# AD4111_1.net
KiCad netlist of a schematic drawn in Altium Designer
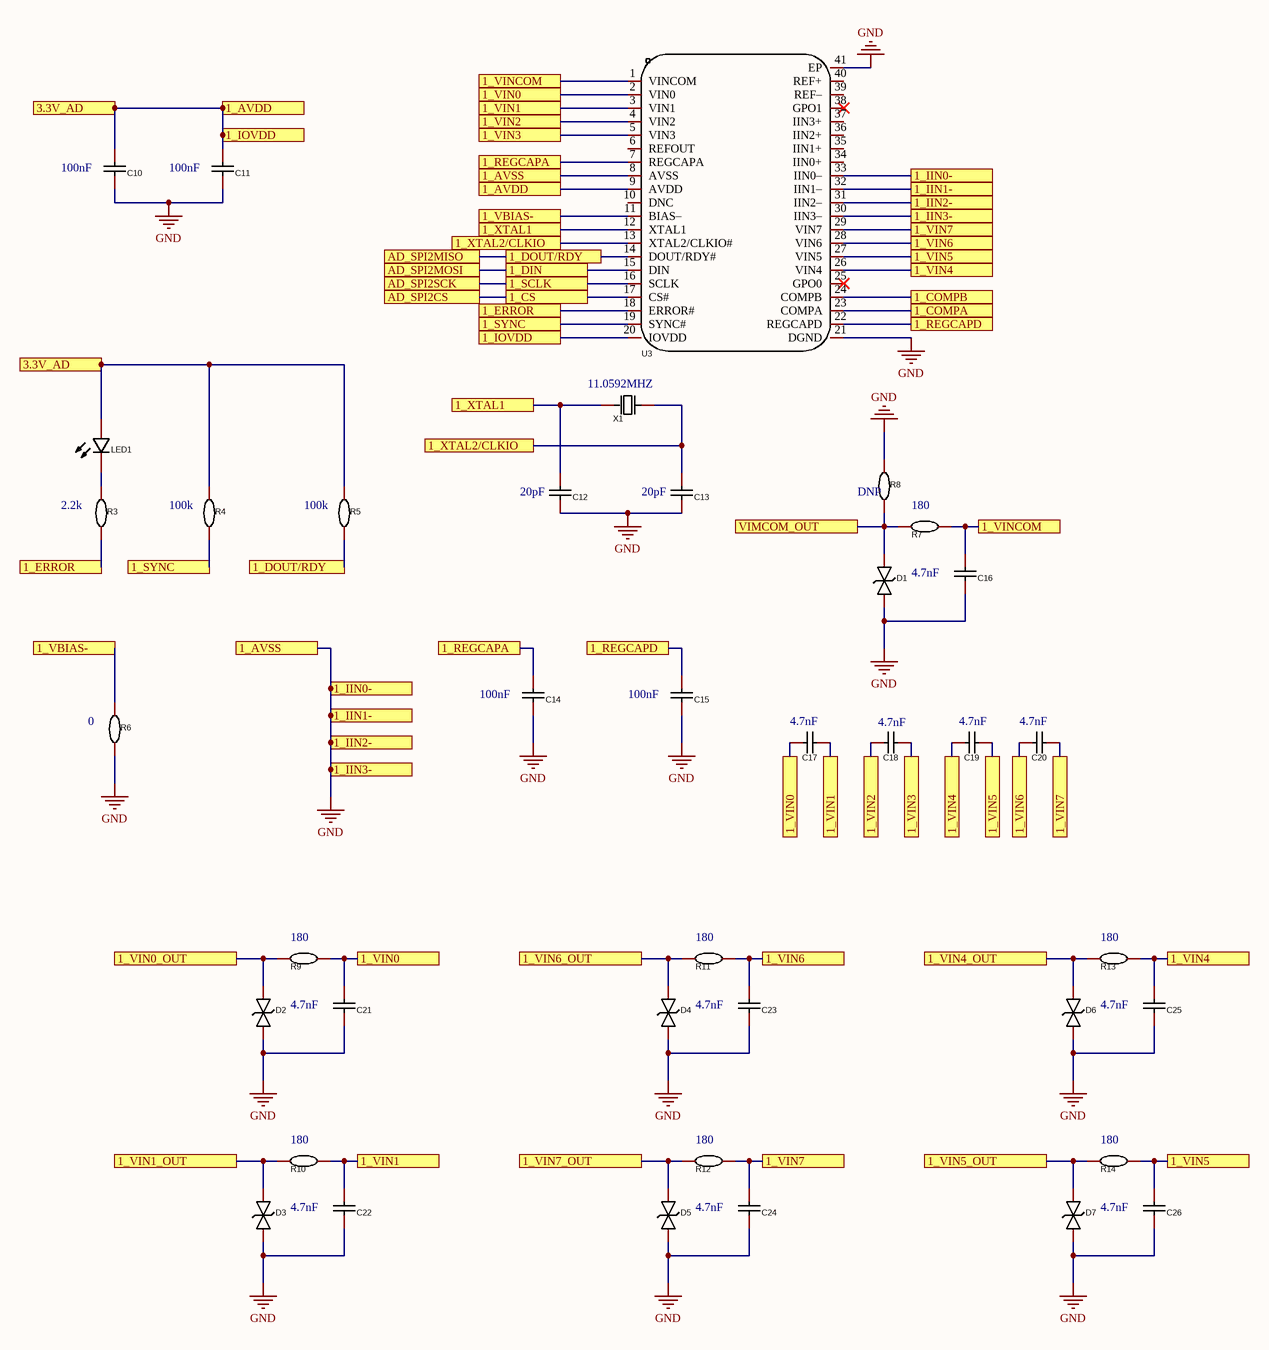
[diagram p0: AD4111_1.SchDoc]

(export (version "E")
  (design (tool "Eeschema 10.0.6"))
  (components
    (comp (ref "C10")
      (value "100nF")
      (footprint "C0603")
      (description "0603电容")
      (fields (field (name "MANUFACTURER") "FH(风华)") (field (name "MANUFACTURER PART") "0603B104K500NT"))
      (libsource (lib "LC_Components") (part "0603B104K500NT"))
    )
    (comp (ref "C11")
      (value "100nF")
      (footprint "C0603")
      (description "0603电容")
      (fields (field (name "MANUFACTURER") "FH(风华)") (field (name "MANUFACTURER PART") "0603B104K500NT"))
      (libsource (lib "LC_Components") (part "0603B104K500NT"))
    )
    (comp (ref "C12")
      (value "20pF")
      (footprint "C0603")
      (description "0603电容")
      (fields (field (name "MANUFACTURER") "FH(风华)") (field (name "MANUFACTURER PART") "0603B104K500NT"))
      (libsource (lib "LC_Components") (part "0603B104K500NT"))
    )
    (comp (ref "C13")
      (value "20pF")
      (footprint "C0603")
      (description "0603电容")
      (fields (field (name "MANUFACTURER") "FH(风华)") (field (name "MANUFACTURER PART") "0603B104K500NT"))
      (libsource (lib "LC_Components") (part "0603B104K500NT"))
    )
    (comp (ref "C14")
      (value "100nF")
      (footprint "C0603")
      (description "0603电容")
      (fields (field (name "MANUFACTURER") "FH(风华)") (field (name "MANUFACTURER PART") "0603B104K500NT"))
      (libsource (lib "LC_Components") (part "0603B104K500NT"))
    )
    (comp (ref "C15")
      (value "100nF")
      (footprint "C0603")
      (description "0603电容")
      (fields (field (name "MANUFACTURER") "FH(风华)") (field (name "MANUFACTURER PART") "0603B104K500NT"))
      (libsource (lib "LC_Components") (part "0603B104K500NT"))
    )
    (comp (ref "C16")
      (value "4.7nF")
      (footprint "C0603")
      (description "0603电容")
      (fields (field (name "MANUFACTURER") "FH(风华)") (field (name "MANUFACTURER PART") "0603B104K500NT"))
      (libsource (lib "LC_Components") (part "0603B104K500NT"))
    )
    (comp (ref "C17")
      (value "4.7nF")
      (footprint "C0603")
      (description "0603电容")
      (fields (field (name "MANUFACTURER") "FH(风华)") (field (name "MANUFACTURER PART") "0603B104K500NT"))
      (libsource (lib "LC_Components") (part "0603B104K500NT"))
    )
    (comp (ref "C18")
      (value "4.7nF")
      (footprint "C0603")
      (description "0603电容")
      (fields (field (name "MANUFACTURER") "FH(风华)") (field (name "MANUFACTURER PART") "0603B104K500NT"))
      (libsource (lib "LC_Components") (part "0603B104K500NT"))
    )
    (comp (ref "C19")
      (value "4.7nF")
      (footprint "C0603")
      (description "0603电容")
      (fields (field (name "MANUFACTURER") "FH(风华)") (field (name "MANUFACTURER PART") "0603B104K500NT"))
      (libsource (lib "LC_Components") (part "0603B104K500NT"))
    )
    (comp (ref "C20")
      (value "4.7nF")
      (footprint "C0603")
      (description "0603电容")
      (fields (field (name "MANUFACTURER") "FH(风华)") (field (name "MANUFACTURER PART") "0603B104K500NT"))
      (libsource (lib "LC_Components") (part "0603B104K500NT"))
    )
    (comp (ref "C21")
      (value "4.7nF")
      (footprint "C0603")
      (description "0603电容")
      (fields (field (name "MANUFACTURER") "FH(风华)") (field (name "MANUFACTURER PART") "0603B104K500NT"))
      (libsource (lib "LC_Components") (part "0603B104K500NT"))
    )
    (comp (ref "C22")
      (value "4.7nF")
      (footprint "C0603")
      (description "0603电容")
      (fields (field (name "MANUFACTURER") "FH(风华)") (field (name "MANUFACTURER PART") "0603B104K500NT"))
      (libsource (lib "LC_Components") (part "0603B104K500NT"))
    )
    (comp (ref "C23")
      (value "4.7nF")
      (footprint "C0603")
      (description "0603电容")
      (fields (field (name "MANUFACTURER") "FH(风华)") (field (name "MANUFACTURER PART") "0603B104K500NT"))
      (libsource (lib "LC_Components") (part "0603B104K500NT"))
    )
    (comp (ref "C24")
      (value "4.7nF")
      (footprint "C0603")
      (description "0603电容")
      (fields (field (name "MANUFACTURER") "FH(风华)") (field (name "MANUFACTURER PART") "0603B104K500NT"))
      (libsource (lib "LC_Components") (part "0603B104K500NT"))
    )
    (comp (ref "C25")
      (value "4.7nF")
      (footprint "C0603")
      (description "0603电容")
      (fields (field (name "MANUFACTURER") "FH(风华)") (field (name "MANUFACTURER PART") "0603B104K500NT"))
      (libsource (lib "LC_Components") (part "0603B104K500NT"))
    )
    (comp (ref "C26")
      (value "4.7nF")
      (footprint "C0603")
      (description "0603电容")
      (fields (field (name "MANUFACTURER") "FH(风华)") (field (name "MANUFACTURER PART") "0603B104K500NT"))
      (libsource (lib "LC_Components") (part "0603B104K500NT"))
    )
    (comp (ref "D1")
      (value "SMAJ33CA_C908829")
      (footprint "SMA_L4.4-W2.8-LS5.1-BI")
      (description "SMAJ33CA")
      (fields (field (name "MANUFACTURER") "GOODWORK(固得沃克)"))
      (libsource (lib "LC_Components") (part "SMAJ33CA_C908829"))
    )
    (comp (ref "D2")
      (value "SMAJ33CA_C908829")
      (footprint "SMA_L4.4-W2.8-LS5.1-BI")
      (description "SMAJ33CA")
      (fields (field (name "MANUFACTURER") "GOODWORK(固得沃克)"))
      (libsource (lib "LC_Components") (part "SMAJ33CA_C908829"))
    )
    (comp (ref "D3")
      (value "SMAJ33CA_C908829")
      (footprint "SMA_L4.4-W2.8-LS5.1-BI")
      (description "SMAJ33CA")
      (fields (field (name "MANUFACTURER") "GOODWORK(固得沃克)"))
      (libsource (lib "LC_Components") (part "SMAJ33CA_C908829"))
    )
    (comp (ref "D4")
      (value "SMAJ33CA_C908829")
      (footprint "SMA_L4.4-W2.8-LS5.1-BI")
      (description "SMAJ33CA")
      (fields (field (name "MANUFACTURER") "GOODWORK(固得沃克)"))
      (libsource (lib "LC_Components") (part "SMAJ33CA_C908829"))
    )
    (comp (ref "D5")
      (value "SMAJ33CA_C908829")
      (footprint "SMA_L4.4-W2.8-LS5.1-BI")
      (description "SMAJ33CA")
      (fields (field (name "MANUFACTURER") "GOODWORK(固得沃克)"))
      (libsource (lib "LC_Components") (part "SMAJ33CA_C908829"))
    )
    (comp (ref "D6")
      (value "SMAJ33CA_C908829")
      (footprint "SMA_L4.4-W2.8-LS5.1-BI")
      (description "SMAJ33CA")
      (fields (field (name "MANUFACTURER") "GOODWORK(固得沃克)"))
      (libsource (lib "LC_Components") (part "SMAJ33CA_C908829"))
    )
    (comp (ref "D7")
      (value "SMAJ33CA_C908829")
      (footprint "SMA_L4.4-W2.8-LS5.1-BI")
      (description "SMAJ33CA")
      (fields (field (name "MANUFACTURER") "GOODWORK(固得沃克)"))
      (libsource (lib "LC_Components") (part "SMAJ33CA_C908829"))
    )
    (comp (ref "LED1")
      (value "NCD0603R1_C84263")
      (footprint "LED0603-RD_RED")
      (description "LED")
      (fields (field (name "MANUFACTURER") "国星光电") (field (name "MANUFACTURER PART") "NCD0603R1"))
      (libsource (lib "LC_Components") (part "NCD0603R1_C84263"))
    )
    (comp (ref "R3")
      (value "2.2k")
      (footprint "R0603")
      (description "0603电阻")
      (fields
        (field (name "MANUFACTURER") "UNI-ROYAL(厚声)")
        (field (name "MANUFACTURER PART") "0603WAF1002T5E")
      )
      (libsource (lib "LC_Components") (part "0603WAF1002T5E"))
    )
    (comp (ref "R4")
      (value "100k")
      (footprint "R0603")
      (description "0603电阻")
      (fields
        (field (name "MANUFACTURER") "UNI-ROYAL(厚声)")
        (field (name "MANUFACTURER PART") "0603WAF1002T5E")
      )
      (libsource (lib "LC_Components") (part "0603WAF1002T5E"))
    )
    (comp (ref "R5")
      (value "100k")
      (footprint "R0603")
      (description "0603电阻")
      (fields
        (field (name "MANUFACTURER") "UNI-ROYAL(厚声)")
        (field (name "MANUFACTURER PART") "0603WAF1002T5E")
      )
      (libsource (lib "LC_Components") (part "0603WAF1002T5E"))
    )
    (comp (ref "R6")
      (value "0")
      (footprint "R0603")
      (description "0603电阻")
      (fields
        (field (name "MANUFACTURER") "UNI-ROYAL(厚声)")
        (field (name "MANUFACTURER PART") "0603WAF1002T5E")
      )
      (libsource (lib "LC_Components") (part "0603WAF1002T5E"))
    )
    (comp (ref "R7")
      (value "180")
      (footprint "R0603")
      (description "0603电阻")
      (fields
        (field (name "MANUFACTURER") "UNI-ROYAL(厚声)")
        (field (name "MANUFACTURER PART") "0603WAF1002T5E")
      )
      (libsource (lib "LC_Components") (part "0603WAF1002T5E"))
    )
    (comp (ref "R8")
      (value "DNP")
      (footprint "R0603")
      (description "0603电阻")
      (fields
        (field (name "MANUFACTURER") "UNI-ROYAL(厚声)")
        (field (name "MANUFACTURER PART") "0603WAF1002T5E")
      )
      (libsource (lib "LC_Components") (part "0603WAF1002T5E"))
    )
    (comp (ref "R9")
      (value "180")
      (footprint "R0603")
      (description "0603电阻")
      (fields
        (field (name "MANUFACTURER") "UNI-ROYAL(厚声)")
        (field (name "MANUFACTURER PART") "0603WAF1002T5E")
      )
      (libsource (lib "LC_Components") (part "0603WAF1002T5E"))
    )
    (comp (ref "R10")
      (value "180")
      (footprint "R0603")
      (description "0603电阻")
      (fields
        (field (name "MANUFACTURER") "UNI-ROYAL(厚声)")
        (field (name "MANUFACTURER PART") "0603WAF1002T5E")
      )
      (libsource (lib "LC_Components") (part "0603WAF1002T5E"))
    )
    (comp (ref "R11")
      (value "180")
      (footprint "R0603")
      (description "0603电阻")
      (fields
        (field (name "MANUFACTURER") "UNI-ROYAL(厚声)")
        (field (name "MANUFACTURER PART") "0603WAF1002T5E")
      )
      (libsource (lib "LC_Components") (part "0603WAF1002T5E"))
    )
    (comp (ref "R12")
      (value "180")
      (footprint "R0603")
      (description "0603电阻")
      (fields
        (field (name "MANUFACTURER") "UNI-ROYAL(厚声)")
        (field (name "MANUFACTURER PART") "0603WAF1002T5E")
      )
      (libsource (lib "LC_Components") (part "0603WAF1002T5E"))
    )
    (comp (ref "R13")
      (value "180")
      (footprint "R0603")
      (description "0603电阻")
      (fields
        (field (name "MANUFACTURER") "UNI-ROYAL(厚声)")
        (field (name "MANUFACTURER PART") "0603WAF1002T5E")
      )
      (libsource (lib "LC_Components") (part "0603WAF1002T5E"))
    )
    (comp (ref "R14")
      (value "180")
      (footprint "R0603")
      (description "0603电阻")
      (fields
        (field (name "MANUFACTURER") "UNI-ROYAL(厚声)")
        (field (name "MANUFACTURER PART") "0603WAF1002T5E")
      )
      (libsource (lib "LC_Components") (part "0603WAF1002T5E"))
    )
    (comp (ref "U3")
      (value "AD4111BCPZ")
      (footprint "LFCSP-40_L6.0-W6.0-P0.50-TL-EP4.6")
      (fields (field (name "MANUFACTURER") "ADI(亚德诺)"))
      (libsource (lib "LC_Components") (part "AD4111BCPZ"))
    )
    (comp (ref "X1")
      (value "11.0592MHZ")
      (footprint "OSC-SMD_L5.0-W3.2")
      (description "11.0592MHZ晶振")
      (fields
        (field (name "MANUFACTURER") "YXC(扬兴晶振)")
        (field (name "MANUFACTURER PART") "X5032110592MSB2GI")
      )
      (libsource (lib "LC_Components") (part "X5032110592MSB2GI"))
    )
  )
  (nets
    (net (code "1") (name "/1_AVDD") (class "Default")
      (node (ref "C10") (pin "2") (pinfunction "2_2") (pintype "passive"))
      (node (ref "C11") (pin "2") (pinfunction "2_2") (pintype "passive"))
      (node (ref "LED1") (pin "2") (pinfunction "A_2") (pintype "passive"))
      (node (ref "R4") (pin "2") (pinfunction "2_2") (pintype "passive"))
      (node (ref "R5") (pin "2") (pinfunction "2_2") (pintype "passive"))
      (node (ref "U3") (pin "20") (pinfunction "IOVDD_20") (pintype "passive"))
      (node (ref "U3") (pin "9") (pinfunction "AVDD_9") (pintype "passive"))
    )
    (net (code "2") (name "/1_COMPA") (class "Default")
      (node (ref "U3") (pin "23") (pinfunction "COMPA_23") (pintype "passive"))
    )
    (net (code "3") (name "/1_COMPB") (class "Default")
      (node (ref "U3") (pin "24") (pinfunction "COMPB_24") (pintype "passive"))
    )
    (net (code "4") (name "/1_CS") (class "Default")
      (node (ref "U3") (pin "17") (pinfunction "CS#_17") (pintype "passive"))
    )
    (net (code "5") (name "/1_DIN") (class "Default")
      (node (ref "U3") (pin "15") (pinfunction "DIN_15") (pintype "passive"))
    )
    (net (code "6") (name "/1_DOUT{slash}RDY") (class "Default")
      (node (ref "R5") (pin "1") (pinfunction "1_1") (pintype "passive"))
      (node (ref "U3") (pin "14") (pinfunction "DOUT/RDY#_14") (pintype "passive"))
    )
    (net (code "7") (name "/1_ERROR") (class "Default")
      (node (ref "R3") (pin "1") (pinfunction "1_1") (pintype "passive"))
      (node (ref "U3") (pin "18") (pinfunction "ERROR#_18") (pintype "passive"))
    )
    (net (code "8") (name "/1_REGCAPA") (class "Default")
      (node (ref "C14") (pin "2") (pinfunction "2_2") (pintype "passive"))
      (node (ref "U3") (pin "7") (pinfunction "REGCAPA_7") (pintype "passive"))
    )
    (net (code "9") (name "/1_REGCAPD") (class "Default")
      (node (ref "C15") (pin "2") (pinfunction "2_2") (pintype "passive"))
      (node (ref "U3") (pin "22") (pinfunction "REGCAPD_22") (pintype "passive"))
    )
    (net (code "10") (name "/1_SCLK") (class "Default")
      (node (ref "U3") (pin "16") (pinfunction "SCLK_16") (pintype "passive"))
    )
    (net (code "11") (name "/1_SYNC") (class "Default")
      (node (ref "R4") (pin "1") (pinfunction "1_1") (pintype "passive"))
      (node (ref "U3") (pin "19") (pinfunction "SYNC#_19") (pintype "passive"))
    )
    (net (code "12") (name "/1_VBIAS-") (class "Default")
      (node (ref "R6") (pin "2") (pinfunction "2_2") (pintype "passive"))
      (node (ref "U3") (pin "11") (pinfunction "BIAS–_11") (pintype "passive"))
    )
    (net (code "13") (name "/1_VIN0") (class "Default")
      (node (ref "C17") (pin "1") (pinfunction "1_1") (pintype "passive"))
      (node (ref "C21") (pin "2") (pinfunction "2_2") (pintype "passive"))
      (node (ref "R9") (pin "2") (pinfunction "2_2") (pintype "passive"))
      (node (ref "U3") (pin "2") (pinfunction "VIN0_2") (pintype "passive"))
    )
    (net (code "14") (name "/1_VIN0_OUT") (class "Default")
      (node (ref "D2") (pin "1") (pinfunction "1_1") (pintype "passive"))
      (node (ref "R9") (pin "1") (pinfunction "1_1") (pintype "passive"))
    )
    (net (code "15") (name "/1_VIN1") (class "Default")
      (node (ref "C17") (pin "2") (pinfunction "2_2") (pintype "passive"))
      (node (ref "C22") (pin "2") (pinfunction "2_2") (pintype "passive"))
      (node (ref "R10") (pin "2") (pinfunction "2_2") (pintype "passive"))
      (node (ref "U3") (pin "3") (pinfunction "VIN1_3") (pintype "passive"))
    )
    (net (code "16") (name "/1_VIN1_OUT") (class "Default")
      (node (ref "D3") (pin "1") (pinfunction "1_1") (pintype "passive"))
      (node (ref "R10") (pin "1") (pinfunction "1_1") (pintype "passive"))
    )
    (net (code "17") (name "/1_VIN2") (class "Default")
      (node (ref "C18") (pin "1") (pinfunction "1_1") (pintype "passive"))
      (node (ref "U3") (pin "4") (pinfunction "VIN2_4") (pintype "passive"))
    )
    (net (code "18") (name "/1_VIN3") (class "Default")
      (node (ref "C18") (pin "2") (pinfunction "2_2") (pintype "passive"))
      (node (ref "U3") (pin "5") (pinfunction "VIN3_5") (pintype "passive"))
    )
    (net (code "19") (name "/1_VIN4") (class "Default")
      (node (ref "C19") (pin "1") (pinfunction "1_1") (pintype "passive"))
      (node (ref "C25") (pin "2") (pinfunction "2_2") (pintype "passive"))
      (node (ref "R13") (pin "2") (pinfunction "2_2") (pintype "passive"))
      (node (ref "U3") (pin "26") (pinfunction "VIN4_26") (pintype "passive"))
    )
    (net (code "20") (name "/1_VIN4_OUT") (class "Default")
      (node (ref "D6") (pin "1") (pinfunction "1_1") (pintype "passive"))
      (node (ref "R13") (pin "1") (pinfunction "1_1") (pintype "passive"))
    )
    (net (code "21") (name "/1_VIN5") (class "Default")
      (node (ref "C19") (pin "2") (pinfunction "2_2") (pintype "passive"))
      (node (ref "C26") (pin "2") (pinfunction "2_2") (pintype "passive"))
      (node (ref "R14") (pin "2") (pinfunction "2_2") (pintype "passive"))
      (node (ref "U3") (pin "27") (pinfunction "VIN5_27") (pintype "passive"))
    )
    (net (code "22") (name "/1_VIN5_OUT") (class "Default")
      (node (ref "D7") (pin "1") (pinfunction "1_1") (pintype "passive"))
      (node (ref "R14") (pin "1") (pinfunction "1_1") (pintype "passive"))
    )
    (net (code "23") (name "/1_VIN6") (class "Default")
      (node (ref "C20") (pin "1") (pinfunction "1_1") (pintype "passive"))
      (node (ref "C23") (pin "2") (pinfunction "2_2") (pintype "passive"))
      (node (ref "R11") (pin "2") (pinfunction "2_2") (pintype "passive"))
      (node (ref "U3") (pin "28") (pinfunction "VIN6_28") (pintype "passive"))
    )
    (net (code "24") (name "/1_VIN6_OUT") (class "Default")
      (node (ref "D4") (pin "1") (pinfunction "1_1") (pintype "passive"))
      (node (ref "R11") (pin "1") (pinfunction "1_1") (pintype "passive"))
    )
    (net (code "25") (name "/1_VIN7") (class "Default")
      (node (ref "C20") (pin "2") (pinfunction "2_2") (pintype "passive"))
      (node (ref "C24") (pin "2") (pinfunction "2_2") (pintype "passive"))
      (node (ref "R12") (pin "2") (pinfunction "2_2") (pintype "passive"))
      (node (ref "U3") (pin "29") (pinfunction "VIN7_29") (pintype "passive"))
    )
    (net (code "26") (name "/1_VIN7_OUT") (class "Default")
      (node (ref "D5") (pin "1") (pinfunction "1_1") (pintype "passive"))
      (node (ref "R12") (pin "1") (pinfunction "1_1") (pintype "passive"))
    )
    (net (code "27") (name "/1_VINCOM") (class "Default")
      (node (ref "C16") (pin "2") (pinfunction "2_2") (pintype "passive"))
      (node (ref "R7") (pin "2") (pinfunction "2_2") (pintype "passive"))
      (node (ref "U3") (pin "1") (pinfunction "VINCOM_1") (pintype "passive"))
    )
    (net (code "28") (name "/1_XTAL1") (class "Default")
      (node (ref "C12") (pin "2") (pinfunction "2_2") (pintype "passive"))
      (node (ref "U3") (pin "12") (pinfunction "XTAL1_12") (pintype "passive"))
      (node (ref "X1") (pin "1") (pinfunction "OSC1_1") (pintype "passive"))
    )
    (net (code "29") (name "/1_XTAL2{slash}CLKIO") (class "Default")
      (node (ref "C13") (pin "2") (pinfunction "2_2") (pintype "passive"))
      (node (ref "U3") (pin "13") (pinfunction "XTAL2/CLKIO#_13") (pintype "passive"))
      (node (ref "X1") (pin "2") (pinfunction "OSC2_2") (pintype "passive"))
    )
    (net (code "30") (name "/VIMCOM_OUT") (class "Default")
      (node (ref "D1") (pin "1") (pinfunction "1_1") (pintype "passive"))
      (node (ref "R7") (pin "1") (pinfunction "1_1") (pintype "passive"))
      (node (ref "R8") (pin "1") (pinfunction "1_1") (pintype "passive"))
    )
    (net (code "31") (name "GND") (class "Default")
      (node (ref "C10") (pin "1") (pinfunction "1_1") (pintype "passive"))
      (node (ref "C11") (pin "1") (pinfunction "1_1") (pintype "passive"))
      (node (ref "C12") (pin "1") (pinfunction "1_1") (pintype "passive"))
      (node (ref "C13") (pin "1") (pinfunction "1_1") (pintype "passive"))
      (node (ref "C14") (pin "1") (pinfunction "1_1") (pintype "passive"))
      (node (ref "C15") (pin "1") (pinfunction "1_1") (pintype "passive"))
      (node (ref "C16") (pin "1") (pinfunction "1_1") (pintype "passive"))
      (node (ref "C21") (pin "1") (pinfunction "1_1") (pintype "passive"))
      (node (ref "C22") (pin "1") (pinfunction "1_1") (pintype "passive"))
      (node (ref "C23") (pin "1") (pinfunction "1_1") (pintype "passive"))
      (node (ref "C24") (pin "1") (pinfunction "1_1") (pintype "passive"))
      (node (ref "C25") (pin "1") (pinfunction "1_1") (pintype "passive"))
      (node (ref "C26") (pin "1") (pinfunction "1_1") (pintype "passive"))
      (node (ref "D1") (pin "2") (pinfunction "2_2") (pintype "passive"))
      (node (ref "D2") (pin "2") (pinfunction "2_2") (pintype "passive"))
      (node (ref "D3") (pin "2") (pinfunction "2_2") (pintype "passive"))
      (node (ref "D4") (pin "2") (pinfunction "2_2") (pintype "passive"))
      (node (ref "D5") (pin "2") (pinfunction "2_2") (pintype "passive"))
      (node (ref "D6") (pin "2") (pinfunction "2_2") (pintype "passive"))
      (node (ref "D7") (pin "2") (pinfunction "2_2") (pintype "passive"))
      (node (ref "R6") (pin "1") (pinfunction "1_1") (pintype "passive"))
      (node (ref "R8") (pin "2") (pinfunction "2_2") (pintype "passive"))
      (node (ref "U3") (pin "21") (pinfunction "DGND_21") (pintype "passive"))
      (node (ref "U3") (pin "30") (pinfunction "IIN3–_30") (pintype "passive"))
      (node (ref "U3") (pin "31") (pinfunction "IIN2–_31") (pintype "passive"))
      (node (ref "U3") (pin "32") (pinfunction "IIN1–_32") (pintype "passive"))
      (node (ref "U3") (pin "33") (pinfunction "IIN0–_33") (pintype "passive"))
      (node (ref "U3") (pin "41") (pinfunction "EP_41") (pintype "passive"))
      (node (ref "U3") (pin "8") (pinfunction "AVSS_8") (pintype "passive"))
    )
    (net (code "32") (name "Net-(LED1-K)") (class "Default")
      (node (ref "LED1") (pin "1") (pinfunction "K_1") (pintype "passive"))
      (node (ref "R3") (pin "2") (pinfunction "2_2") (pintype "passive"))
    )
    (net (code "33") (name "unconnected-(U3-DNC-Pad10)") (class "Default")
      (node (ref "U3") (pin "10") (pinfunction "DNC_10") (pintype "passive"))
    )
    (net (code "34") (name "unconnected-(U3-GPO0-Pad25)") (class "Default")
      (node (ref "U3") (pin "25") (pinfunction "GPO0_25") (pintype "passive+no_connect"))
    )
    (net (code "35") (name "unconnected-(U3-GPO1-Pad38)") (class "Default")
      (node (ref "U3") (pin "38") (pinfunction "GPO1_38") (pintype "passive+no_connect"))
    )
    (net (code "36") (name "unconnected-(U3-IIN0+-Pad34)") (class "Default")
      (node (ref "U3") (pin "34") (pinfunction "IIN0+_34") (pintype "passive"))
    )
    (net (code "37") (name "unconnected-(U3-IIN1+-Pad35)") (class "Default")
      (node (ref "U3") (pin "35") (pinfunction "IIN1+_35") (pintype "passive"))
    )
    (net (code "38") (name "unconnected-(U3-IIN2+-Pad36)") (class "Default")
      (node (ref "U3") (pin "36") (pinfunction "IIN2+_36") (pintype "passive"))
    )
    (net (code "39") (name "unconnected-(U3-IIN3+-Pad37)") (class "Default")
      (node (ref "U3") (pin "37") (pinfunction "IIN3+_37") (pintype "passive"))
    )
    (net (code "40") (name "unconnected-(U3-REF+-Pad40)") (class "Default")
      (node (ref "U3") (pin "40") (pinfunction "REF+_40") (pintype "passive"))
    )
    (net (code "41") (name "unconnected-(U3-REFOUT-Pad6)") (class "Default")
      (node (ref "U3") (pin "6") (pinfunction "REFOUT_6") (pintype "passive"))
    )
    (net (code "42") (name "unconnected-(U3-REF–-Pad39)") (class "Default")
      (node (ref "U3") (pin "39") (pinfunction "REF–_39") (pintype "passive"))
    )
  )
)
